# canable_candapter.net
KiCad netlist of a schematic drawn in EAGLE
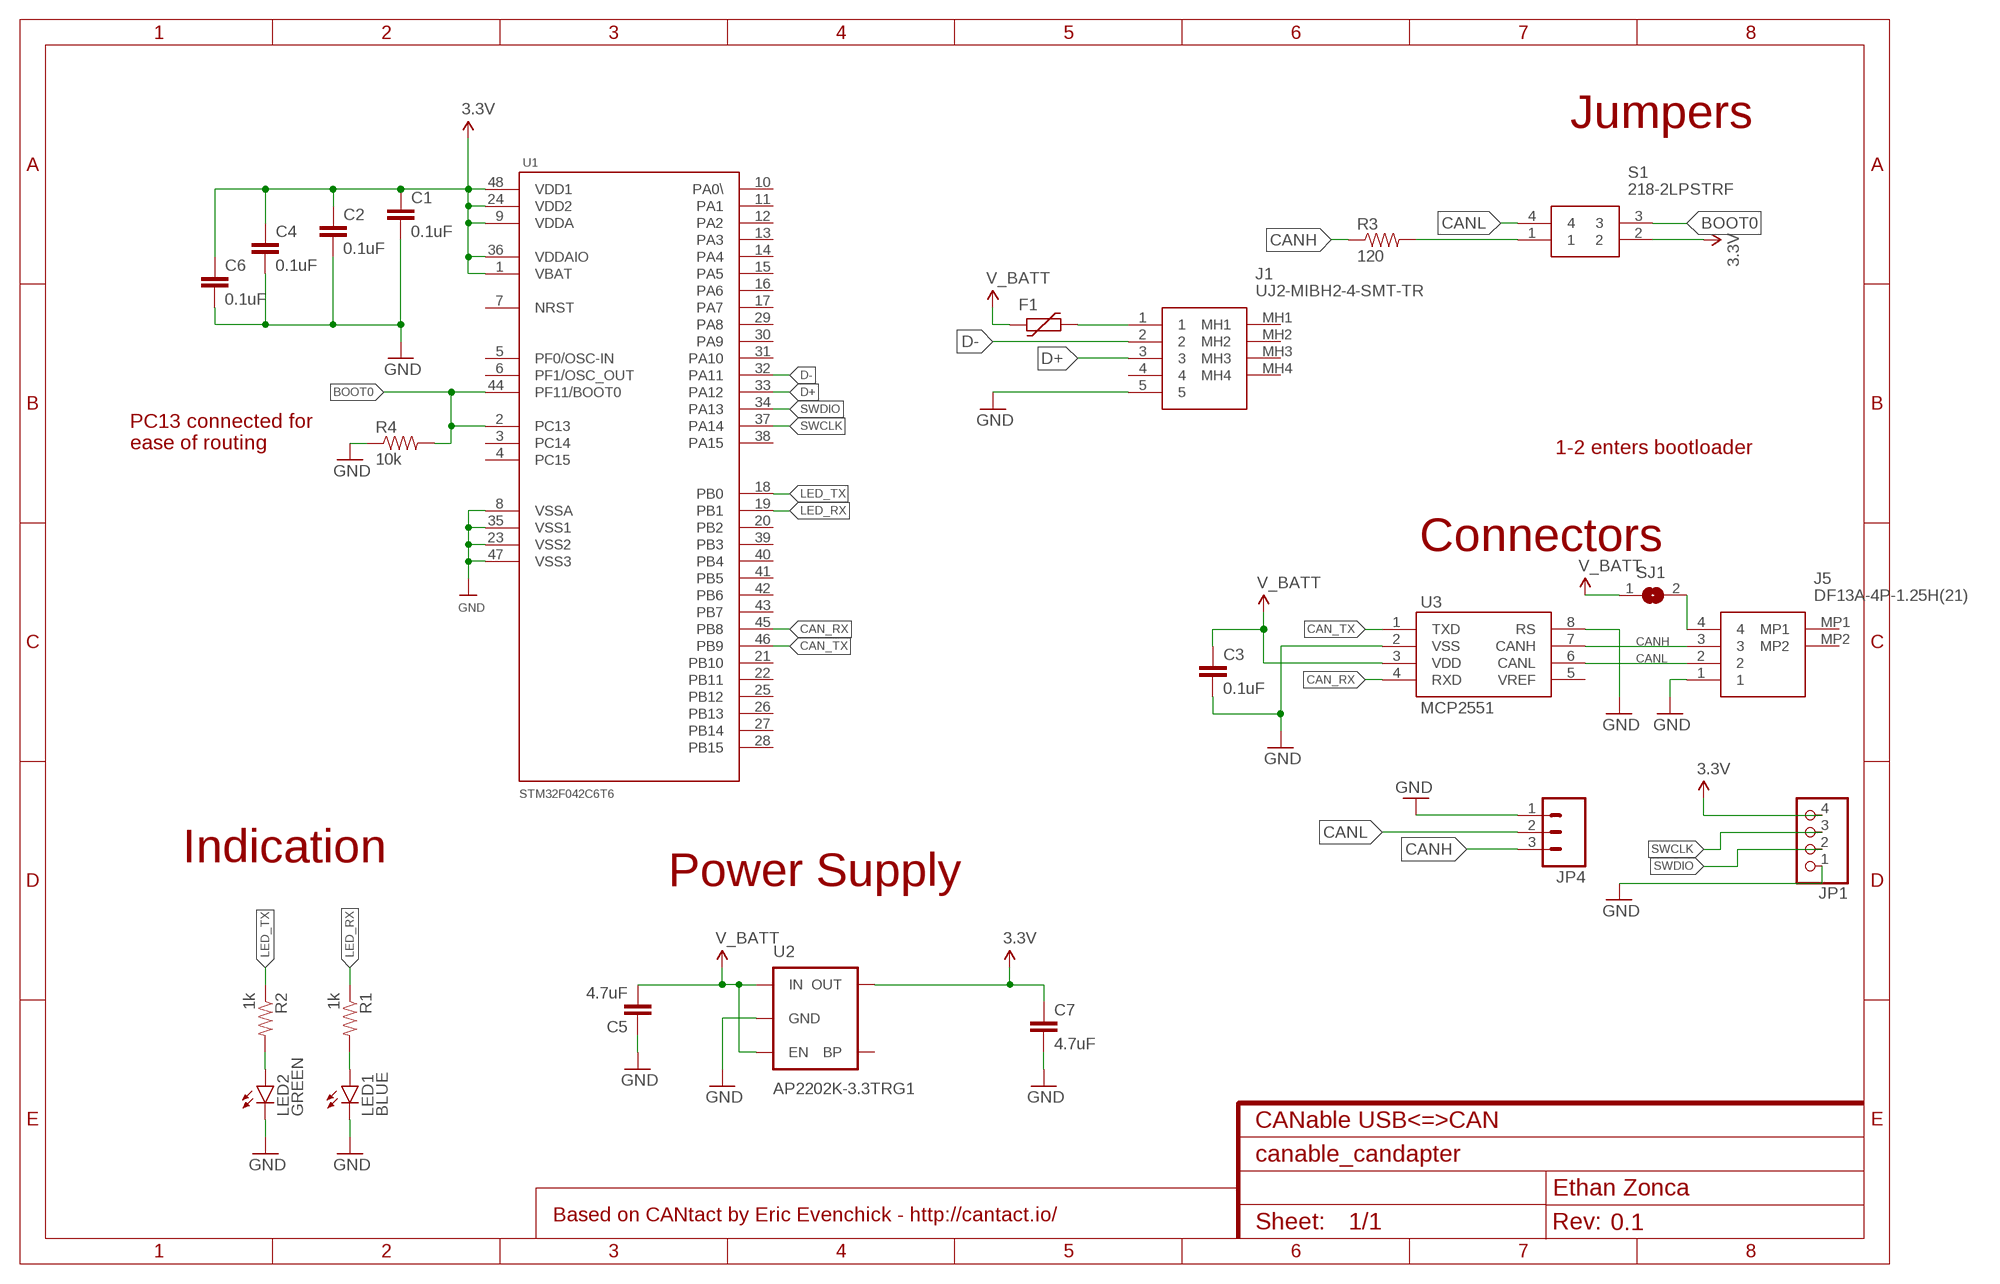
[diagram p0: schematic, sheet 1]

(export (version "E")
  (design (tool "Eeschema 10.0.6"))
  (components
    (comp (ref "C1")
      (value "0.1uF")
      (footprint "eagle-import:0603-CAP")
      (libsource (lib "eagle-import") (part "CAP0603-CAP"))
    )
    (comp (ref "C2")
      (value "0.1uF")
      (footprint "eagle-import:0603-CAP")
      (libsource (lib "eagle-import") (part "CAP0603-CAP"))
    )
    (comp (ref "C3")
      (value "0.1uF")
      (footprint "eagle-import:0603-CAP")
      (libsource (lib "eagle-import") (part "CAP0603-CAP"))
    )
    (comp (ref "C4")
      (value "0.1uF")
      (footprint "eagle-import:0603-CAP")
      (libsource (lib "eagle-import") (part "CAP0603-CAP"))
    )
    (comp (ref "C5")
      (value "4.7uF")
      (footprint "eagle-import:0603-CAP")
      (libsource (lib "eagle-import") (part "CAP0603-CAP"))
    )
    (comp (ref "C6")
      (value "0.1uF")
      (footprint "eagle-import:0603-CAP")
      (libsource (lib "eagle-import") (part "CAP0603-CAP"))
    )
    (comp (ref "C7")
      (value "4.7uF")
      (footprint "eagle-import:0603-CAP")
      (libsource (lib "eagle-import") (part "CAP0603-CAP"))
    )
    (comp (ref "F1")
      (value "FUSE_PTC-0805")
      (footprint "eagle-import:PTC0805")
      (libsource (lib "eagle-import") (part "FUSE_PTC-0805"))
    )
    (comp (ref "J1")
      (value "UJ2-MIBH2-4-SMT-TR")
      (footprint "eagle-import:UJ2MIBH24SMTTR")
      (fields (field (name "MOUSER_PART_NUMBER") "490-UJ2-MIBH2-4-SMT"))
      (libsource (lib "eagle-import") (part "UJ2-MIBH2-4-SMT-TR"))
    )
    (comp (ref "J5")
      (value "DF13A-4P-1.25H(21)")
      (footprint "eagle-import:DF13A4P125H21")
      (fields
        (field (name "MOUSER_PART_NUMBER") "798-DF13A4P125H21")
        (field (name "RS_PART_NUMBER") "1886349")
      )
      (libsource (lib "eagle-import") (part "DF13A-4P-1.25H(21)"))
    )
    (comp (ref "JP1")
      (value "PINHD-1X04_2.54-S")
      (footprint "eagle-import:1X04-S")
      (libsource (lib "eagle-import") (part "PINHD-1X04_2.54-S"))
    )
    (comp (ref "JP4")
      (value "M03LOCK")
      (footprint "eagle-import:1X03_LOCK")
      (libsource (lib "eagle-import") (part "M03LOCK"))
    )
    (comp (ref "LED1")
      (value "BLUE")
      (footprint "eagle-import:LED-0603")
      (libsource (lib "eagle-import") (part "LED0603"))
    )
    (comp (ref "LED2")
      (value "GREEN")
      (footprint "eagle-import:LED-0603")
      (libsource (lib "eagle-import") (part "LED0603"))
    )
    (comp (ref "R1")
      (value "1k")
      (footprint "eagle-import:0603-RES")
      (libsource (lib "eagle-import") (part "RESISTOR0603-RES"))
    )
    (comp (ref "R2")
      (value "1k")
      (footprint "eagle-import:0603-RES")
      (libsource (lib "eagle-import") (part "RESISTOR0603-RES"))
    )
    (comp (ref "R3")
      (value "120")
      (footprint "eagle-import:0603-RES")
      (libsource (lib "eagle-import") (part "RESISTOR0603-RES"))
    )
    (comp (ref "R4")
      (value "10k")
      (footprint "eagle-import:0603-RES")
      (libsource (lib "eagle-import") (part "RESISTOR0603-RES"))
    )
    (comp (ref "S1")
      (value "218-2LPSTRF")
      (footprint "eagle-import:2182LPSTRF")
      (fields (field (name "MOUSER_PART_NUMBER") "774-218-2LPSTRF"))
      (libsource (lib "eagle-import") (part "218-2LPSTRF"))
    )
    (comp (ref "SJ1") (value "SJ") (footprint "eagle-import:SJ") (libsource (lib "eagle-import") (part "SJ")))
    (comp (ref "U1")
      (value "STM32F042C6T6")
      (footprint "eagle-import:LQFP48")
      (libsource (lib "eagle-import") (part "STM32F042C6T6"))
    )
    (comp (ref "U2")
      (value "AP2202K-3.3TRG1")
      (footprint "eagle-import:SOT23-5")
      (libsource (lib "eagle-import") (part "MIC52053.3V"))
    )
    (comp (ref "U3")
      (value "MCP2551")
      (footprint "eagle-import:SO08")
      (libsource (lib "eagle-import") (part "MCP2551"))
    )
  )
  (nets
    (net (code "1") (name "3.3V") (class "Default")
      (node (ref "C1") (pin "1") (pinfunction "1_1") (pintype "passive"))
      (node (ref "C2") (pin "1") (pinfunction "1_1") (pintype "passive"))
      (node (ref "C4") (pin "1") (pinfunction "1_1") (pintype "passive"))
      (node (ref "C6") (pin "1") (pinfunction "1_1") (pintype "passive"))
      (node (ref "C7") (pin "1") (pinfunction "1_1") (pintype "passive"))
      (node (ref "JP1") (pin "4") (pinfunction "4_4") (pintype "passive"))
      (node (ref "S1") (pin "2") (pinfunction "2_2") (pintype "bidirectional"))
      (node (ref "U1") (pin "1") (pinfunction "VBAT_1") (pintype "bidirectional"))
      (node (ref "U1") (pin "24") (pinfunction "VDD2_24") (pintype "bidirectional"))
      (node (ref "U1") (pin "36") (pinfunction "VDDAIO_36") (pintype "bidirectional"))
      (node (ref "U1") (pin "48") (pinfunction "VDD1_48") (pintype "bidirectional"))
      (node (ref "U1") (pin "9") (pinfunction "VDDA_9") (pintype "bidirectional"))
      (node (ref "U2") (pin "5") (pinfunction "OUT_5") (pintype "passive"))
    )
    (net (code "2") (name "BOOT0") (class "Default")
      (node (ref "R4") (pin "2") (pinfunction "2_2") (pintype "passive"))
      (node (ref "S1") (pin "3") (pinfunction "3_3") (pintype "bidirectional"))
      (node (ref "U1") (pin "2") (pinfunction "PC13_2") (pintype "bidirectional"))
      (node (ref "U1") (pin "44") (pinfunction "PF11/BOOT0_44") (pintype "bidirectional"))
    )
    (net (code "3") (name "CANH") (class "Default")
      (node (ref "J5") (pin "3") (pinfunction "3_3") (pintype "bidirectional"))
      (node (ref "JP4") (pin "3") (pinfunction "3_3") (pintype "passive"))
      (node (ref "R3") (pin "1") (pinfunction "1_1") (pintype "passive"))
      (node (ref "U3") (pin "7") (pinfunction "CANH_7") (pintype "bidirectional"))
    )
    (net (code "4") (name "CANL") (class "Default")
      (node (ref "J5") (pin "2") (pinfunction "2_2") (pintype "bidirectional"))
      (node (ref "JP4") (pin "2") (pinfunction "2_2") (pintype "passive"))
      (node (ref "S1") (pin "4") (pinfunction "4_4") (pintype "bidirectional"))
      (node (ref "U3") (pin "6") (pinfunction "CANL_6") (pintype "bidirectional"))
    )
    (net (code "5") (name "CAN_RX") (class "Default")
      (node (ref "U1") (pin "45") (pinfunction "PB8_45") (pintype "bidirectional"))
      (node (ref "U3") (pin "4") (pinfunction "RXD_4") (pintype "bidirectional"))
    )
    (net (code "6") (name "CAN_TX") (class "Default")
      (node (ref "U1") (pin "46") (pinfunction "PB9_46") (pintype "bidirectional"))
      (node (ref "U3") (pin "1") (pinfunction "TXD_1") (pintype "bidirectional"))
    )
    (net (code "7") (name "D+") (class "Default")
      (node (ref "J1") (pin "3") (pinfunction "3_3") (pintype "bidirectional"))
      (node (ref "U1") (pin "33") (pinfunction "PA12_33") (pintype "bidirectional"))
    )
    (net (code "8") (name "D-") (class "Default")
      (node (ref "J1") (pin "2") (pinfunction "2_2") (pintype "bidirectional"))
      (node (ref "U1") (pin "32") (pinfunction "PA11_32") (pintype "bidirectional"))
    )
    (net (code "9") (name "GND") (class "Default")
      (node (ref "C1") (pin "2") (pinfunction "2_2") (pintype "passive"))
      (node (ref "C2") (pin "2") (pinfunction "2_2") (pintype "passive"))
      (node (ref "C3") (pin "2") (pinfunction "2_2") (pintype "passive"))
      (node (ref "C4") (pin "2") (pinfunction "2_2") (pintype "passive"))
      (node (ref "C5") (pin "1") (pinfunction "1_1") (pintype "passive"))
      (node (ref "C6") (pin "2") (pinfunction "2_2") (pintype "passive"))
      (node (ref "C7") (pin "2") (pinfunction "2_2") (pintype "passive"))
      (node (ref "J1") (pin "5") (pinfunction "5_5") (pintype "bidirectional"))
      (node (ref "J5") (pin "1") (pinfunction "1_1") (pintype "bidirectional"))
      (node (ref "JP1") (pin "1") (pinfunction "1_1") (pintype "passive"))
      (node (ref "JP4") (pin "1") (pinfunction "1_1") (pintype "passive"))
      (node (ref "LED1") (pin "C") (pinfunction "C_C") (pintype "passive"))
      (node (ref "LED2") (pin "C") (pinfunction "C_C") (pintype "passive"))
      (node (ref "R4") (pin "1") (pinfunction "1_1") (pintype "passive"))
      (node (ref "U1") (pin "23") (pinfunction "VSS2_23") (pintype "bidirectional"))
      (node (ref "U1") (pin "35") (pinfunction "VSS1_35") (pintype "bidirectional"))
      (node (ref "U1") (pin "47") (pinfunction "VSS3_47") (pintype "bidirectional"))
      (node (ref "U1") (pin "8") (pinfunction "VSSA_8") (pintype "bidirectional"))
      (node (ref "U2") (pin "2") (pinfunction "GND_2") (pintype "input"))
      (node (ref "U3") (pin "2") (pinfunction "VSS_2") (pintype "bidirectional"))
      (node (ref "U3") (pin "8") (pinfunction "RS_8") (pintype "bidirectional"))
    )
    (net (code "10") (name "LED_RX") (class "Default")
      (node (ref "R1") (pin "1") (pinfunction "1_1") (pintype "passive"))
      (node (ref "U1") (pin "19") (pinfunction "PB1_19") (pintype "bidirectional"))
    )
    (net (code "11") (name "LED_TX") (class "Default")
      (node (ref "R2") (pin "1") (pinfunction "1_1") (pintype "passive"))
      (node (ref "U1") (pin "18") (pinfunction "PB0_18") (pintype "bidirectional"))
    )
    (net (code "12") (name "Net-(F1-Pad2)") (class "Default")
      (node (ref "F1") (pin "2") (pinfunction "2_2") (pintype "passive"))
      (node (ref "J1") (pin "1") (pinfunction "1_1") (pintype "bidirectional"))
    )
    (net (code "13") (name "Net-(J5-Pad4)") (class "Default")
      (node (ref "J5") (pin "4") (pinfunction "4_4") (pintype "bidirectional"))
      (node (ref "SJ1") (pin "2") (pinfunction "2_2") (pintype "passive"))
    )
    (net (code "14") (name "Net-(LED1-PadA)") (class "Default")
      (node (ref "LED1") (pin "A") (pinfunction "A_A") (pintype "passive"))
      (node (ref "R1") (pin "2") (pinfunction "2_2") (pintype "passive"))
    )
    (net (code "15") (name "Net-(LED2-PadA)") (class "Default")
      (node (ref "LED2") (pin "A") (pinfunction "A_A") (pintype "passive"))
      (node (ref "R2") (pin "2") (pinfunction "2_2") (pintype "passive"))
    )
    (net (code "16") (name "Net-(R3-Pad2)") (class "Default")
      (node (ref "R3") (pin "2") (pinfunction "2_2") (pintype "passive"))
      (node (ref "S1") (pin "1") (pinfunction "1_1") (pintype "bidirectional"))
    )
    (net (code "17") (name "SWCLK") (class "Default")
      (node (ref "JP1") (pin "3") (pinfunction "3_3") (pintype "passive"))
      (node (ref "U1") (pin "37") (pinfunction "PA14_37") (pintype "bidirectional"))
    )
    (net (code "18") (name "SWDIO") (class "Default")
      (node (ref "JP1") (pin "2") (pinfunction "2_2") (pintype "passive"))
      (node (ref "U1") (pin "34") (pinfunction "PA13_34") (pintype "bidirectional"))
    )
    (net (code "19") (name "V_BATT") (class "Default")
      (node (ref "C3") (pin "1") (pinfunction "1_1") (pintype "passive"))
      (node (ref "C5") (pin "2") (pinfunction "2_2") (pintype "passive"))
      (node (ref "F1") (pin "1") (pinfunction "1_1") (pintype "passive"))
      (node (ref "SJ1") (pin "1") (pinfunction "1_1") (pintype "passive"))
      (node (ref "U2") (pin "1") (pinfunction "IN_1") (pintype "input"))
      (node (ref "U2") (pin "3") (pinfunction "EN_3") (pintype "input"))
      (node (ref "U3") (pin "3") (pinfunction "VDD_3") (pintype "bidirectional"))
    )
    (net (code "20") (name "unconnected-(J1-Pad4)") (class "Default")
      (node (ref "J1") (pin "4") (pinfunction "4_4") (pintype "bidirectional"))
    )
    (net (code "21") (name "unconnected-(J1-PadMH1)") (class "Default")
      (node (ref "J1") (pin "MH1") (pinfunction "MH1_MH1") (pintype "bidirectional"))
    )
    (net (code "22") (name "unconnected-(J1-PadMH2)") (class "Default")
      (node (ref "J1") (pin "MH2") (pinfunction "MH2_MH2") (pintype "bidirectional"))
    )
    (net (code "23") (name "unconnected-(J1-PadMH3)") (class "Default")
      (node (ref "J1") (pin "MH3") (pinfunction "MH3_MH3") (pintype "bidirectional"))
    )
    (net (code "24") (name "unconnected-(J1-PadMH4)") (class "Default")
      (node (ref "J1") (pin "MH4") (pinfunction "MH4_MH4") (pintype "bidirectional"))
    )
    (net (code "25") (name "unconnected-(J5-PadMP1)") (class "Default")
      (node (ref "J5") (pin "MP1") (pinfunction "MP1_MP1") (pintype "bidirectional"))
    )
    (net (code "26") (name "unconnected-(J5-PadMP2)") (class "Default")
      (node (ref "J5") (pin "MP2") (pinfunction "MP2_MP2") (pintype "bidirectional"))
    )
    (net (code "27") (name "unconnected-(U1-NRST-Pad7)") (class "Default")
      (node (ref "U1") (pin "7") (pinfunction "NRST_7") (pintype "bidirectional"))
    )
    (net (code "28") (name "unconnected-(U1-PA0\\-Pad10)") (class "Default")
      (node (ref "U1") (pin "10") (pinfunction "PA0\\_10") (pintype "bidirectional"))
    )
    (net (code "29") (name "unconnected-(U1-PA1-Pad11)") (class "Default")
      (node (ref "U1") (pin "11") (pinfunction "PA1_11") (pintype "bidirectional"))
    )
    (net (code "30") (name "unconnected-(U1-PA2-Pad12)") (class "Default")
      (node (ref "U1") (pin "12") (pinfunction "PA2_12") (pintype "bidirectional"))
    )
    (net (code "31") (name "unconnected-(U1-PA3-Pad13)") (class "Default")
      (node (ref "U1") (pin "13") (pinfunction "PA3_13") (pintype "bidirectional"))
    )
    (net (code "32") (name "unconnected-(U1-PA4-Pad14)") (class "Default")
      (node (ref "U1") (pin "14") (pinfunction "PA4_14") (pintype "bidirectional"))
    )
    (net (code "33") (name "unconnected-(U1-PA5-Pad15)") (class "Default")
      (node (ref "U1") (pin "15") (pinfunction "PA5_15") (pintype "bidirectional"))
    )
    (net (code "34") (name "unconnected-(U1-PA6-Pad16)") (class "Default")
      (node (ref "U1") (pin "16") (pinfunction "PA6_16") (pintype "bidirectional"))
    )
    (net (code "35") (name "unconnected-(U1-PA7-Pad17)") (class "Default")
      (node (ref "U1") (pin "17") (pinfunction "PA7_17") (pintype "bidirectional"))
    )
    (net (code "36") (name "unconnected-(U1-PA8-Pad29)") (class "Default")
      (node (ref "U1") (pin "29") (pinfunction "PA8_29") (pintype "bidirectional"))
    )
    (net (code "37") (name "unconnected-(U1-PA9-Pad30)") (class "Default")
      (node (ref "U1") (pin "30") (pinfunction "PA9_30") (pintype "bidirectional"))
    )
    (net (code "38") (name "unconnected-(U1-PA10-Pad31)") (class "Default")
      (node (ref "U1") (pin "31") (pinfunction "PA10_31") (pintype "bidirectional"))
    )
    (net (code "39") (name "unconnected-(U1-PA15-Pad38)") (class "Default")
      (node (ref "U1") (pin "38") (pinfunction "PA15_38") (pintype "bidirectional"))
    )
    (net (code "40") (name "unconnected-(U1-PB2-Pad20)") (class "Default")
      (node (ref "U1") (pin "20") (pinfunction "PB2_20") (pintype "bidirectional"))
    )
    (net (code "41") (name "unconnected-(U1-PB3-Pad39)") (class "Default")
      (node (ref "U1") (pin "39") (pinfunction "PB3_39") (pintype "bidirectional"))
    )
    (net (code "42") (name "unconnected-(U1-PB4-Pad40)") (class "Default")
      (node (ref "U1") (pin "40") (pinfunction "PB4_40") (pintype "bidirectional"))
    )
    (net (code "43") (name "unconnected-(U1-PB5-Pad41)") (class "Default")
      (node (ref "U1") (pin "41") (pinfunction "PB5_41") (pintype "bidirectional"))
    )
    (net (code "44") (name "unconnected-(U1-PB6-Pad42)") (class "Default")
      (node (ref "U1") (pin "42") (pinfunction "PB6_42") (pintype "bidirectional"))
    )
    (net (code "45") (name "unconnected-(U1-PB7-Pad43)") (class "Default")
      (node (ref "U1") (pin "43") (pinfunction "PB7_43") (pintype "bidirectional"))
    )
    (net (code "46") (name "unconnected-(U1-PB10-Pad21)") (class "Default")
      (node (ref "U1") (pin "21") (pinfunction "PB10_21") (pintype "bidirectional"))
    )
    (net (code "47") (name "unconnected-(U1-PB11-Pad22)") (class "Default")
      (node (ref "U1") (pin "22") (pinfunction "PB11_22") (pintype "bidirectional"))
    )
    (net (code "48") (name "unconnected-(U1-PB12-Pad25)") (class "Default")
      (node (ref "U1") (pin "25") (pinfunction "PB12_25") (pintype "bidirectional"))
    )
    (net (code "49") (name "unconnected-(U1-PB13-Pad26)") (class "Default")
      (node (ref "U1") (pin "26") (pinfunction "PB13_26") (pintype "bidirectional"))
    )
    (net (code "50") (name "unconnected-(U1-PB14-Pad27)") (class "Default")
      (node (ref "U1") (pin "27") (pinfunction "PB14_27") (pintype "bidirectional"))
    )
    (net (code "51") (name "unconnected-(U1-PB15-Pad28)") (class "Default")
      (node (ref "U1") (pin "28") (pinfunction "PB15_28") (pintype "bidirectional"))
    )
    (net (code "52") (name "unconnected-(U1-PC14-Pad3)") (class "Default")
      (node (ref "U1") (pin "3") (pinfunction "PC14_3") (pintype "bidirectional"))
    )
    (net (code "53") (name "unconnected-(U1-PC15-Pad4)") (class "Default")
      (node (ref "U1") (pin "4") (pinfunction "PC15_4") (pintype "bidirectional"))
    )
    (net (code "54") (name "unconnected-(U1-PF0{slash}OSC-IN-Pad5)") (class "Default")
      (node (ref "U1") (pin "5") (pinfunction "PF0/OSC-IN_5") (pintype "bidirectional"))
    )
    (net (code "55") (name "unconnected-(U1-PF1{slash}OSC_OUT-Pad6)") (class "Default")
      (node (ref "U1") (pin "6") (pinfunction "PF1/OSC_OUT_6") (pintype "bidirectional"))
    )
    (net (code "56") (name "unconnected-(U2-BP-Pad4)") (class "Default")
      (node (ref "U2") (pin "4") (pinfunction "BP_4") (pintype "input"))
    )
    (net (code "57") (name "unconnected-(U3-VREF-Pad5)") (class "Default")
      (node (ref "U3") (pin "5") (pinfunction "VREF_5") (pintype "bidirectional"))
    )
  )
)
